# R123B.net
KiCad netlist of a schematic drawn in EAGLE
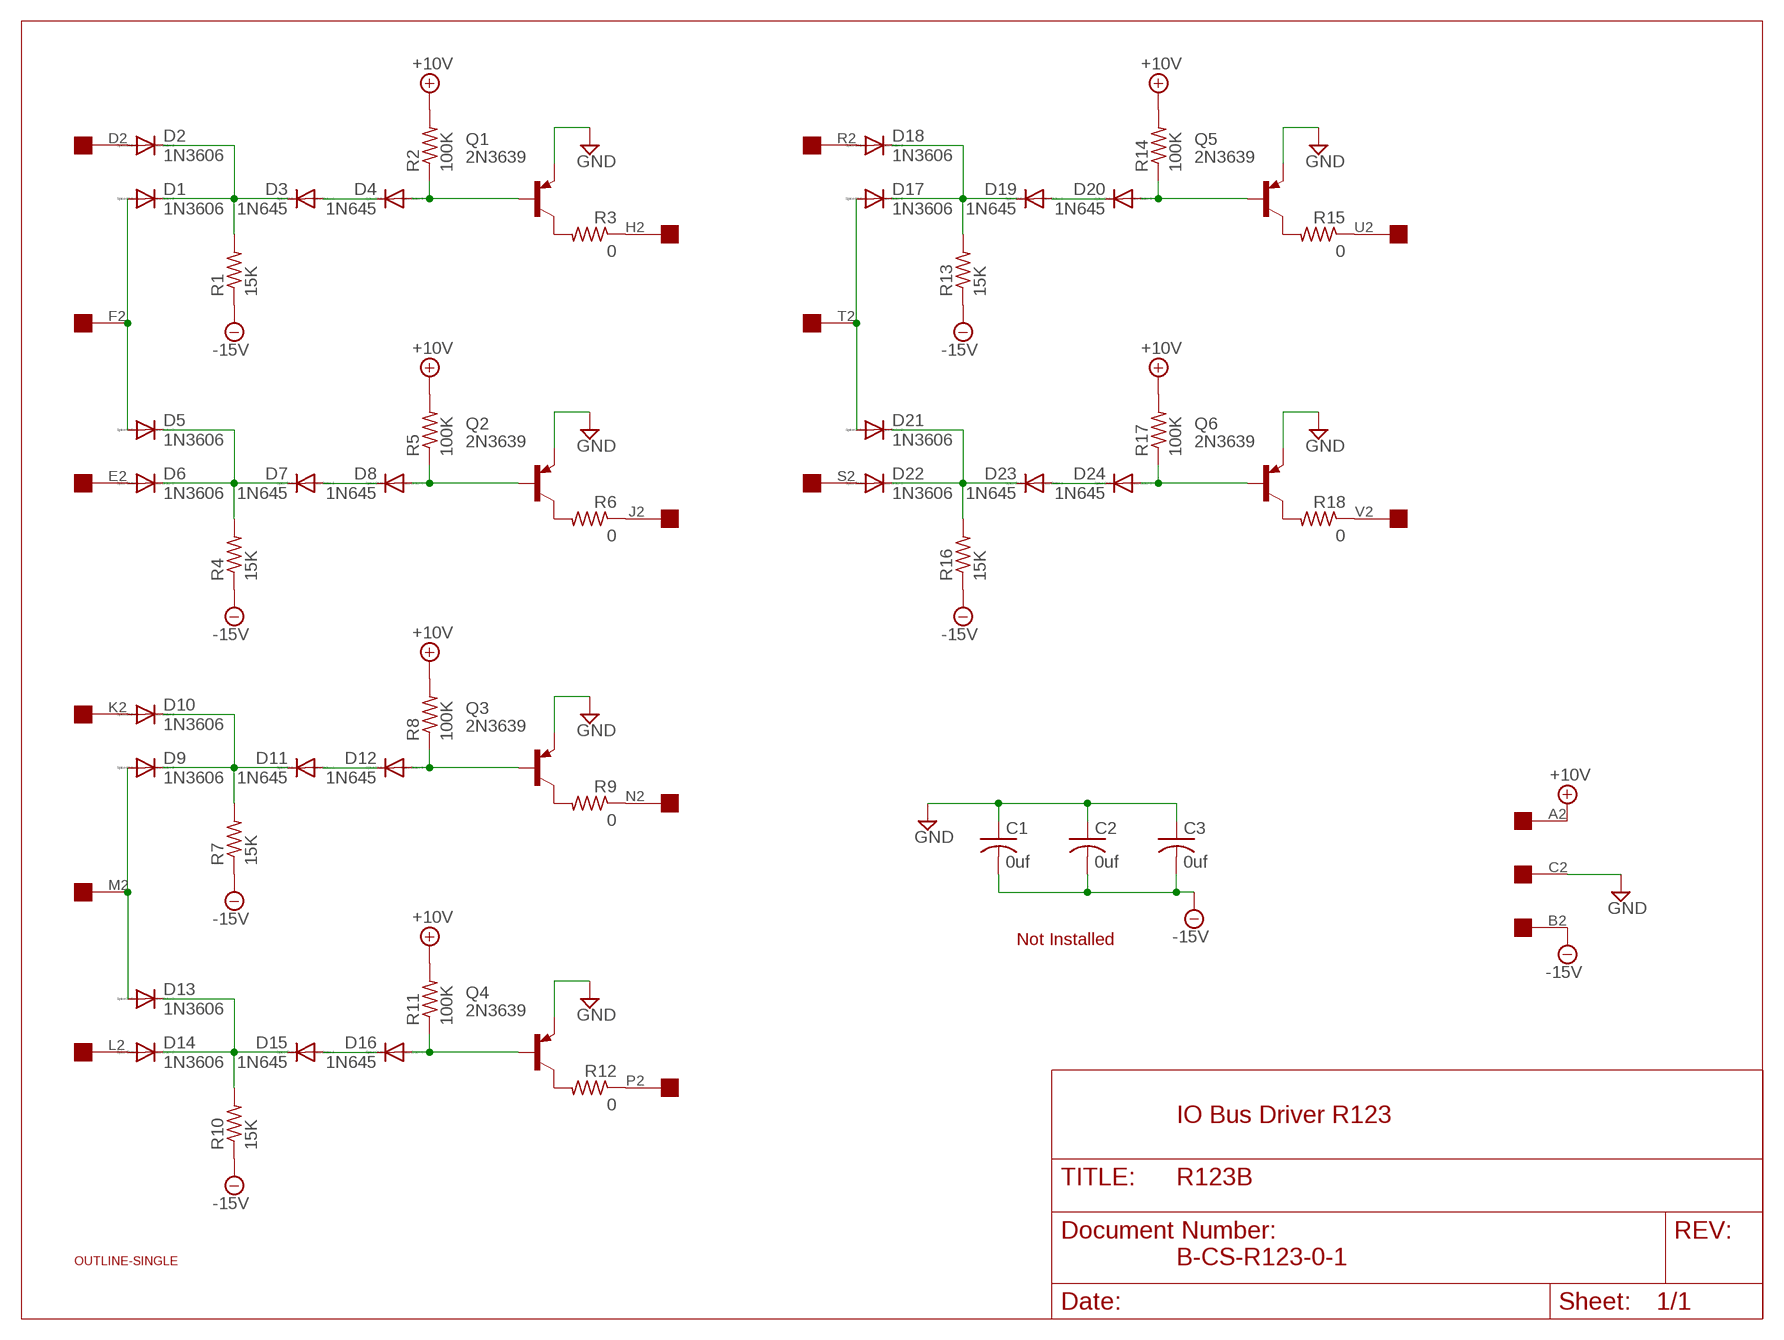
[diagram p0: schematic, sheet 1]

(export (version "E")
  (design (tool "Eeschema 10.0.6"))
  (components
    (comp (ref "C1")
      (value "0uf")
      (footprint "eagle-import:C050-025X075")
      (libsource (lib "eagle-import") (part "C-US050-025X075"))
    )
    (comp (ref "C2")
      (value "0uf")
      (footprint "eagle-import:C050-025X075")
      (libsource (lib "eagle-import") (part "C-US050-025X075"))
    )
    (comp (ref "C3")
      (value "0uf")
      (footprint "eagle-import:C050-025X075")
      (libsource (lib "eagle-import") (part "C-US050-025X075"))
    )
    (comp (ref "D1")
      (value "1N3606")
      (footprint "eagle-import:DO35-10")
      (libsource (lib "eagle-import") (part "1N4148DO35-10"))
    )
    (comp (ref "D2")
      (value "1N3606")
      (footprint "eagle-import:DO35-10")
      (libsource (lib "eagle-import") (part "1N4148DO35-10"))
    )
    (comp (ref "D3")
      (value "1N645")
      (footprint "eagle-import:DO35-10")
      (libsource (lib "eagle-import") (part "1N4148DO35-10"))
    )
    (comp (ref "D4")
      (value "1N645")
      (footprint "eagle-import:DO35-10")
      (libsource (lib "eagle-import") (part "1N4148DO35-10"))
    )
    (comp (ref "D5")
      (value "1N3606")
      (footprint "eagle-import:DO35-10")
      (libsource (lib "eagle-import") (part "1N4148DO35-10"))
    )
    (comp (ref "D6")
      (value "1N3606")
      (footprint "eagle-import:DO35-10")
      (libsource (lib "eagle-import") (part "1N4148DO35-10"))
    )
    (comp (ref "D7")
      (value "1N645")
      (footprint "eagle-import:DO35-10")
      (libsource (lib "eagle-import") (part "1N4148DO35-10"))
    )
    (comp (ref "D8")
      (value "1N645")
      (footprint "eagle-import:DO35-10")
      (libsource (lib "eagle-import") (part "1N4148DO35-10"))
    )
    (comp (ref "D9")
      (value "1N3606")
      (footprint "eagle-import:DO35-10")
      (libsource (lib "eagle-import") (part "1N4148DO35-10"))
    )
    (comp (ref "D10")
      (value "1N3606")
      (footprint "eagle-import:DO35-10")
      (libsource (lib "eagle-import") (part "1N4148DO35-10"))
    )
    (comp (ref "D11")
      (value "1N645")
      (footprint "eagle-import:DO35-10")
      (libsource (lib "eagle-import") (part "1N4148DO35-10"))
    )
    (comp (ref "D12")
      (value "1N645")
      (footprint "eagle-import:DO35-10")
      (libsource (lib "eagle-import") (part "1N4148DO35-10"))
    )
    (comp (ref "D13")
      (value "1N3606")
      (footprint "eagle-import:DO35-10")
      (libsource (lib "eagle-import") (part "1N4148DO35-10"))
    )
    (comp (ref "D14")
      (value "1N3606")
      (footprint "eagle-import:DO35-10")
      (libsource (lib "eagle-import") (part "1N4148DO35-10"))
    )
    (comp (ref "D15")
      (value "1N645")
      (footprint "eagle-import:DO35-10")
      (libsource (lib "eagle-import") (part "1N4148DO35-10"))
    )
    (comp (ref "D16")
      (value "1N645")
      (footprint "eagle-import:DO35-10")
      (libsource (lib "eagle-import") (part "1N4148DO35-10"))
    )
    (comp (ref "D17")
      (value "1N3606")
      (footprint "eagle-import:DO35-10")
      (libsource (lib "eagle-import") (part "1N4148DO35-10"))
    )
    (comp (ref "D18")
      (value "1N3606")
      (footprint "eagle-import:DO35-10")
      (libsource (lib "eagle-import") (part "1N4148DO35-10"))
    )
    (comp (ref "D19")
      (value "1N645")
      (footprint "eagle-import:DO35-10")
      (libsource (lib "eagle-import") (part "1N4148DO35-10"))
    )
    (comp (ref "D20")
      (value "1N645")
      (footprint "eagle-import:DO35-10")
      (libsource (lib "eagle-import") (part "1N4148DO35-10"))
    )
    (comp (ref "D21")
      (value "1N3606")
      (footprint "eagle-import:DO35-10")
      (libsource (lib "eagle-import") (part "1N4148DO35-10"))
    )
    (comp (ref "D22")
      (value "1N3606")
      (footprint "eagle-import:DO35-10")
      (libsource (lib "eagle-import") (part "1N4148DO35-10"))
    )
    (comp (ref "D23")
      (value "1N645")
      (footprint "eagle-import:DO35-10")
      (libsource (lib "eagle-import") (part "1N4148DO35-10"))
    )
    (comp (ref "D24")
      (value "1N645")
      (footprint "eagle-import:DO35-10")
      (libsource (lib "eagle-import") (part "1N4148DO35-10"))
    )
    (comp (ref "Q1")
      (value "2N3639")
      (footprint "eagle-import:TO39")
      (libsource (lib "eagle-import") (part "2N3637"))
    )
    (comp (ref "Q2")
      (value "2N3639")
      (footprint "eagle-import:TO39")
      (libsource (lib "eagle-import") (part "2N3637"))
    )
    (comp (ref "Q3")
      (value "2N3639")
      (footprint "eagle-import:TO39")
      (libsource (lib "eagle-import") (part "2N3637"))
    )
    (comp (ref "Q4")
      (value "2N3639")
      (footprint "eagle-import:TO39")
      (libsource (lib "eagle-import") (part "2N3637"))
    )
    (comp (ref "Q5")
      (value "2N3639")
      (footprint "eagle-import:TO39")
      (libsource (lib "eagle-import") (part "2N3637"))
    )
    (comp (ref "Q6")
      (value "2N3639")
      (footprint "eagle-import:TO39")
      (libsource (lib "eagle-import") (part "2N3637"))
    )
    (comp (ref "R1")
      (value "15K")
      (footprint "eagle-import:0207_10")
      (libsource (lib "eagle-import") (part "R-US_0207/10"))
    )
    (comp (ref "R2")
      (value "100K")
      (footprint "eagle-import:0207_10")
      (libsource (lib "eagle-import") (part "R-US_0207/10"))
    )
    (comp (ref "R3")
      (value "0")
      (footprint "eagle-import:0207_10")
      (libsource (lib "eagle-import") (part "R-US_0207/10"))
    )
    (comp (ref "R4")
      (value "15K")
      (footprint "eagle-import:0207_10")
      (libsource (lib "eagle-import") (part "R-US_0207/10"))
    )
    (comp (ref "R5")
      (value "100K")
      (footprint "eagle-import:0207_10")
      (libsource (lib "eagle-import") (part "R-US_0207/10"))
    )
    (comp (ref "R6")
      (value "0")
      (footprint "eagle-import:0207_10")
      (libsource (lib "eagle-import") (part "R-US_0207/10"))
    )
    (comp (ref "R7")
      (value "15K")
      (footprint "eagle-import:0207_10")
      (libsource (lib "eagle-import") (part "R-US_0207/10"))
    )
    (comp (ref "R8")
      (value "100K")
      (footprint "eagle-import:0207_10")
      (libsource (lib "eagle-import") (part "R-US_0207/10"))
    )
    (comp (ref "R9")
      (value "0")
      (footprint "eagle-import:0207_10")
      (libsource (lib "eagle-import") (part "R-US_0207/10"))
    )
    (comp (ref "R10")
      (value "15K")
      (footprint "eagle-import:0207_10")
      (libsource (lib "eagle-import") (part "R-US_0207/10"))
    )
    (comp (ref "R11")
      (value "100K")
      (footprint "eagle-import:0207_10")
      (libsource (lib "eagle-import") (part "R-US_0207/10"))
    )
    (comp (ref "R12")
      (value "0")
      (footprint "eagle-import:0207_10")
      (libsource (lib "eagle-import") (part "R-US_0207/10"))
    )
    (comp (ref "R13")
      (value "15K")
      (footprint "eagle-import:0207_10")
      (libsource (lib "eagle-import") (part "R-US_0207/10"))
    )
    (comp (ref "R14")
      (value "100K")
      (footprint "eagle-import:0207_10")
      (libsource (lib "eagle-import") (part "R-US_0207/10"))
    )
    (comp (ref "R15")
      (value "0")
      (footprint "eagle-import:0207_10")
      (libsource (lib "eagle-import") (part "R-US_0207/10"))
    )
    (comp (ref "R16")
      (value "15K")
      (footprint "eagle-import:0207_10")
      (libsource (lib "eagle-import") (part "R-US_0207/10"))
    )
    (comp (ref "R17")
      (value "100K")
      (footprint "eagle-import:0207_10")
      (libsource (lib "eagle-import") (part "R-US_0207/10"))
    )
    (comp (ref "R18")
      (value "0")
      (footprint "eagle-import:0207_10")
      (libsource (lib "eagle-import") (part "R-US_0207/10"))
    )
    (comp (ref "U$1")
      (value "OUTLINE-SINGLE")
      (footprint "eagle-import:SINGLE")
      (libsource (lib "eagle-import") (part "OUTLINE-SINGLE"))
    )
    (comp (ref "U$2")
      (value "EDGE-1")
      (footprint "eagle-import:EDGE-CON1")
      (libsource (lib "eagle-import") (part "EDGE-1"))
    )
  )
  (nets
    (net (code "1") (name "+10V") (class "Default")
      (node (ref "R11") (pin "2") (pinfunction "2_2") (pintype "passive"))
      (node (ref "R14") (pin "2") (pinfunction "2_2") (pintype "passive"))
      (node (ref "R17") (pin "2") (pinfunction "2_2") (pintype "passive"))
      (node (ref "R2") (pin "2") (pinfunction "2_2") (pintype "passive"))
      (node (ref "R5") (pin "2") (pinfunction "2_2") (pintype "passive"))
      (node (ref "R8") (pin "2") (pinfunction "2_2") (pintype "passive"))
      (node (ref "U$2") (pin "A2") (pinfunction "1_A2") (pintype "bidirectional"))
    )
    (net (code "2") (name "-15V") (class "Default")
      (node (ref "C1") (pin "2") (pinfunction "2_2") (pintype "passive"))
      (node (ref "C2") (pin "2") (pinfunction "2_2") (pintype "passive"))
      (node (ref "C3") (pin "2") (pinfunction "2_2") (pintype "passive"))
      (node (ref "R1") (pin "1") (pinfunction "1_1") (pintype "passive"))
      (node (ref "R10") (pin "1") (pinfunction "1_1") (pintype "passive"))
      (node (ref "R13") (pin "1") (pinfunction "1_1") (pintype "passive"))
      (node (ref "R16") (pin "1") (pinfunction "1_1") (pintype "passive"))
      (node (ref "R4") (pin "1") (pinfunction "1_1") (pintype "passive"))
      (node (ref "R7") (pin "1") (pinfunction "1_1") (pintype "passive"))
      (node (ref "U$2") (pin "B2") (pinfunction "1_B2") (pintype "bidirectional"))
    )
    (net (code "3") (name "GND") (class "Default")
      (node (ref "C1") (pin "1") (pinfunction "1_1") (pintype "passive"))
      (node (ref "C2") (pin "1") (pinfunction "1_1") (pintype "passive"))
      (node (ref "C3") (pin "1") (pinfunction "1_1") (pintype "passive"))
      (node (ref "Q1") (pin "1") (pinfunction "E_1") (pintype "passive"))
      (node (ref "Q2") (pin "1") (pinfunction "E_1") (pintype "passive"))
      (node (ref "Q3") (pin "1") (pinfunction "E_1") (pintype "passive"))
      (node (ref "Q4") (pin "1") (pinfunction "E_1") (pintype "passive"))
      (node (ref "Q5") (pin "1") (pinfunction "E_1") (pintype "passive"))
      (node (ref "Q6") (pin "1") (pinfunction "E_1") (pintype "passive"))
      (node (ref "U$2") (pin "C2") (pinfunction "1_C2") (pintype "bidirectional"))
    )
    (net (code "4") (name "Net-(D1-PadC)") (class "Default")
      (node (ref "D1") (pin "C") (pinfunction "C_C") (pintype "passive"))
      (node (ref "D2") (pin "C") (pinfunction "C_C") (pintype "passive"))
      (node (ref "D3") (pin "C") (pinfunction "C_C") (pintype "passive"))
      (node (ref "R1") (pin "2") (pinfunction "2_2") (pintype "passive"))
    )
    (net (code "5") (name "Net-(D3-PadA)") (class "Default")
      (node (ref "D3") (pin "A") (pinfunction "A_A") (pintype "passive"))
      (node (ref "D4") (pin "C") (pinfunction "C_C") (pintype "passive"))
    )
    (net (code "6") (name "Net-(D5-PadC)") (class "Default")
      (node (ref "D5") (pin "C") (pinfunction "C_C") (pintype "passive"))
      (node (ref "D6") (pin "C") (pinfunction "C_C") (pintype "passive"))
      (node (ref "D7") (pin "C") (pinfunction "C_C") (pintype "passive"))
      (node (ref "R4") (pin "2") (pinfunction "2_2") (pintype "passive"))
    )
    (net (code "7") (name "Net-(D7-PadA)") (class "Default")
      (node (ref "D7") (pin "A") (pinfunction "A_A") (pintype "passive"))
      (node (ref "D8") (pin "C") (pinfunction "C_C") (pintype "passive"))
    )
    (net (code "8") (name "Net-(D10-PadC)") (class "Default")
      (node (ref "D10") (pin "C") (pinfunction "C_C") (pintype "passive"))
      (node (ref "D11") (pin "C") (pinfunction "C_C") (pintype "passive"))
      (node (ref "D9") (pin "C") (pinfunction "C_C") (pintype "passive"))
      (node (ref "R7") (pin "2") (pinfunction "2_2") (pintype "passive"))
    )
    (net (code "9") (name "Net-(D11-PadA)") (class "Default")
      (node (ref "D11") (pin "A") (pinfunction "A_A") (pintype "passive"))
      (node (ref "D12") (pin "C") (pinfunction "C_C") (pintype "passive"))
    )
    (net (code "10") (name "Net-(D13-PadC)") (class "Default")
      (node (ref "D13") (pin "C") (pinfunction "C_C") (pintype "passive"))
      (node (ref "D14") (pin "C") (pinfunction "C_C") (pintype "passive"))
      (node (ref "D15") (pin "C") (pinfunction "C_C") (pintype "passive"))
      (node (ref "R10") (pin "2") (pinfunction "2_2") (pintype "passive"))
    )
    (net (code "11") (name "Net-(D15-PadA)") (class "Default")
      (node (ref "D15") (pin "A") (pinfunction "A_A") (pintype "passive"))
      (node (ref "D16") (pin "C") (pinfunction "C_C") (pintype "passive"))
    )
    (net (code "12") (name "Net-(D17-PadC)") (class "Default")
      (node (ref "D17") (pin "C") (pinfunction "C_C") (pintype "passive"))
      (node (ref "D18") (pin "C") (pinfunction "C_C") (pintype "passive"))
      (node (ref "D19") (pin "C") (pinfunction "C_C") (pintype "passive"))
      (node (ref "R13") (pin "2") (pinfunction "2_2") (pintype "passive"))
    )
    (net (code "13") (name "Net-(D19-PadA)") (class "Default")
      (node (ref "D19") (pin "A") (pinfunction "A_A") (pintype "passive"))
      (node (ref "D20") (pin "C") (pinfunction "C_C") (pintype "passive"))
    )
    (net (code "14") (name "Net-(D21-PadC)") (class "Default")
      (node (ref "D21") (pin "C") (pinfunction "C_C") (pintype "passive"))
      (node (ref "D22") (pin "C") (pinfunction "C_C") (pintype "passive"))
      (node (ref "D23") (pin "C") (pinfunction "C_C") (pintype "passive"))
      (node (ref "R16") (pin "2") (pinfunction "2_2") (pintype "passive"))
    )
    (net (code "15") (name "Net-(D23-PadA)") (class "Default")
      (node (ref "D23") (pin "A") (pinfunction "A_A") (pintype "passive"))
      (node (ref "D24") (pin "C") (pinfunction "C_C") (pintype "passive"))
    )
    (net (code "16") (name "Net-(Q1-B)") (class "Default")
      (node (ref "D4") (pin "A") (pinfunction "A_A") (pintype "passive"))
      (node (ref "Q1") (pin "2") (pinfunction "B_2") (pintype "passive"))
      (node (ref "R2") (pin "1") (pinfunction "1_1") (pintype "passive"))
    )
    (net (code "17") (name "Net-(Q1-C)") (class "Default")
      (node (ref "Q1") (pin "3") (pinfunction "C_3") (pintype "passive"))
      (node (ref "R3") (pin "2") (pinfunction "2_2") (pintype "passive"))
    )
    (net (code "18") (name "Net-(Q2-B)") (class "Default")
      (node (ref "D8") (pin "A") (pinfunction "A_A") (pintype "passive"))
      (node (ref "Q2") (pin "2") (pinfunction "B_2") (pintype "passive"))
      (node (ref "R5") (pin "1") (pinfunction "1_1") (pintype "passive"))
    )
    (net (code "19") (name "Net-(Q2-C)") (class "Default")
      (node (ref "Q2") (pin "3") (pinfunction "C_3") (pintype "passive"))
      (node (ref "R6") (pin "2") (pinfunction "2_2") (pintype "passive"))
    )
    (net (code "20") (name "Net-(Q3-B)") (class "Default")
      (node (ref "D12") (pin "A") (pinfunction "A_A") (pintype "passive"))
      (node (ref "Q3") (pin "2") (pinfunction "B_2") (pintype "passive"))
      (node (ref "R8") (pin "1") (pinfunction "1_1") (pintype "passive"))
    )
    (net (code "21") (name "Net-(Q3-C)") (class "Default")
      (node (ref "Q3") (pin "3") (pinfunction "C_3") (pintype "passive"))
      (node (ref "R9") (pin "2") (pinfunction "2_2") (pintype "passive"))
    )
    (net (code "22") (name "Net-(Q4-B)") (class "Default")
      (node (ref "D16") (pin "A") (pinfunction "A_A") (pintype "passive"))
      (node (ref "Q4") (pin "2") (pinfunction "B_2") (pintype "passive"))
      (node (ref "R11") (pin "1") (pinfunction "1_1") (pintype "passive"))
    )
    (net (code "23") (name "Net-(Q4-C)") (class "Default")
      (node (ref "Q4") (pin "3") (pinfunction "C_3") (pintype "passive"))
      (node (ref "R12") (pin "2") (pinfunction "2_2") (pintype "passive"))
    )
    (net (code "24") (name "Net-(Q5-B)") (class "Default")
      (node (ref "D20") (pin "A") (pinfunction "A_A") (pintype "passive"))
      (node (ref "Q5") (pin "2") (pinfunction "B_2") (pintype "passive"))
      (node (ref "R14") (pin "1") (pinfunction "1_1") (pintype "passive"))
    )
    (net (code "25") (name "Net-(Q5-C)") (class "Default")
      (node (ref "Q5") (pin "3") (pinfunction "C_3") (pintype "passive"))
      (node (ref "R15") (pin "2") (pinfunction "2_2") (pintype "passive"))
    )
    (net (code "26") (name "Net-(Q6-B)") (class "Default")
      (node (ref "D24") (pin "A") (pinfunction "A_A") (pintype "passive"))
      (node (ref "Q6") (pin "2") (pinfunction "B_2") (pintype "passive"))
      (node (ref "R17") (pin "1") (pinfunction "1_1") (pintype "passive"))
    )
    (net (code "27") (name "Net-(Q6-C)") (class "Default")
      (node (ref "Q6") (pin "3") (pinfunction "C_3") (pintype "passive"))
      (node (ref "R18") (pin "2") (pinfunction "2_2") (pintype "passive"))
    )
    (net (code "28") (name "Net-(U$2D-1)") (class "Default")
      (node (ref "D2") (pin "A") (pinfunction "A_A") (pintype "passive"))
      (node (ref "U$2") (pin "D2") (pinfunction "1_D2") (pintype "bidirectional"))
    )
    (net (code "29") (name "Net-(U$2E-1)") (class "Default")
      (node (ref "D6") (pin "A") (pinfunction "A_A") (pintype "passive"))
      (node (ref "U$2") (pin "E2") (pinfunction "1_E2") (pintype "bidirectional"))
    )
    (net (code "30") (name "Net-(U$2F-1)") (class "Default")
      (node (ref "D1") (pin "A") (pinfunction "A_A") (pintype "passive"))
      (node (ref "D5") (pin "A") (pinfunction "A_A") (pintype "passive"))
      (node (ref "U$2") (pin "F2") (pinfunction "1_F2") (pintype "bidirectional"))
    )
    (net (code "31") (name "Net-(U$2G-1)") (class "Default")
      (node (ref "R3") (pin "1") (pinfunction "1_1") (pintype "passive"))
      (node (ref "U$2") (pin "H2") (pinfunction "1_H2") (pintype "bidirectional"))
    )
    (net (code "32") (name "Net-(U$2H-1)") (class "Default")
      (node (ref "R6") (pin "1") (pinfunction "1_1") (pintype "passive"))
      (node (ref "U$2") (pin "J2") (pinfunction "1_J2") (pintype "bidirectional"))
    )
    (net (code "33") (name "Net-(U$2I-1)") (class "Default")
      (node (ref "D10") (pin "A") (pinfunction "A_A") (pintype "passive"))
      (node (ref "U$2") (pin "K2") (pinfunction "1_K2") (pintype "bidirectional"))
    )
    (net (code "34") (name "Net-(U$2J-1)") (class "Default")
      (node (ref "D14") (pin "A") (pinfunction "A_A") (pintype "passive"))
      (node (ref "U$2") (pin "L2") (pinfunction "1_L2") (pintype "bidirectional"))
    )
    (net (code "35") (name "Net-(U$2K-1)") (class "Default")
      (node (ref "D13") (pin "A") (pinfunction "A_A") (pintype "passive"))
      (node (ref "D9") (pin "A") (pinfunction "A_A") (pintype "passive"))
      (node (ref "U$2") (pin "M2") (pinfunction "1_M2") (pintype "bidirectional"))
    )
    (net (code "36") (name "Net-(U$2L-1)") (class "Default")
      (node (ref "R9") (pin "1") (pinfunction "1_1") (pintype "passive"))
      (node (ref "U$2") (pin "N2") (pinfunction "1_N2") (pintype "bidirectional"))
    )
    (net (code "37") (name "Net-(U$2M-1)") (class "Default")
      (node (ref "R12") (pin "1") (pinfunction "1_1") (pintype "passive"))
      (node (ref "U$2") (pin "P2") (pinfunction "1_P2") (pintype "bidirectional"))
    )
    (net (code "38") (name "Net-(U$2N-1)") (class "Default")
      (node (ref "D18") (pin "A") (pinfunction "A_A") (pintype "passive"))
      (node (ref "U$2") (pin "R2") (pinfunction "1_R2") (pintype "bidirectional"))
    )
    (net (code "39") (name "Net-(U$2O-1)") (class "Default")
      (node (ref "D22") (pin "A") (pinfunction "A_A") (pintype "passive"))
      (node (ref "U$2") (pin "S2") (pinfunction "1_S2") (pintype "bidirectional"))
    )
    (net (code "40") (name "Net-(U$2P-1)") (class "Default")
      (node (ref "D17") (pin "A") (pinfunction "A_A") (pintype "passive"))
      (node (ref "D21") (pin "A") (pinfunction "A_A") (pintype "passive"))
      (node (ref "U$2") (pin "T2") (pinfunction "1_T2") (pintype "bidirectional"))
    )
    (net (code "41") (name "Net-(U$2Q-1)") (class "Default")
      (node (ref "R15") (pin "1") (pinfunction "1_1") (pintype "passive"))
      (node (ref "U$2") (pin "U2") (pinfunction "1_U2") (pintype "bidirectional"))
    )
    (net (code "42") (name "Net-(U$2R-1)") (class "Default")
      (node (ref "R18") (pin "1") (pinfunction "1_1") (pintype "passive"))
      (node (ref "U$2") (pin "V2") (pinfunction "1_V2") (pintype "bidirectional"))
    )
  )
)
